# v2_1.net
KiCad netlist of a schematic drawn in Altium Designer
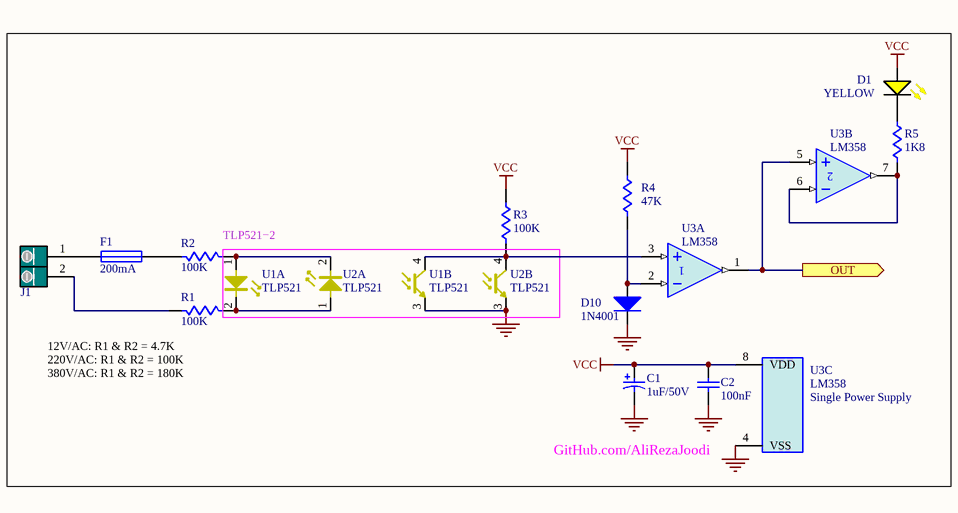
[diagram p0: v2.1.SchDoc]

(export (version "E")
  (design (tool "Eeschema 10.0.6"))
  (components
    (comp (ref "C1")
      (value "1uF/50V")
      (footprint "C_THD_EL_(P2.54-D6-H11)")
      (description "Capacitor, Electrolytic")
      (libsource (lib "Passive") (part "Capacitor_Electrolytic"))
    )
    (comp (ref "C2")
      (value "100nF")
      (footprint "C_THD_CER_(P2.54-D3.5-T1.5)")
      (description "Capacitor, Ceramic Multilayer")
      (libsource (lib "Passive") (part "Capacitor_Ceramic"))
    )
    (comp (ref "D1")
      (value "YELLOW")
      (footprint "LED_THD_5MM_YELLOW")
      (description "LED, Yellow")
      (fields (field (name "MANUFACTURER") "Generic Components") (field (name "PUBLISHER") "Altium Limited"))
      (libsource (lib "Display") (part "LED_YELLOW"))
    )
    (comp (ref "D10")
      (value "1N4001")
      (footprint "DIODE-0.4")
      (description "Default Diode")
      (fields (field (name "MANUFACTURER") "Generic Components") (field (name "PUBLISHER") "Altium Limited"))
      (libsource (lib "Miscellaneous Devices") (part "Diode"))
    )
    (comp (ref "F1")
      (value "200mA")
      (footprint "PIN-W2/E2.8")
      (description "Fuse")
      (fields (field (name "PUBLISHER") "Altium Limited"))
      (libsource (lib "Miscellaneous Devices") (part "Fuse 1"))
    )
    (comp (ref "J1")
      (value "Connector_1x2Pin_Power2")
      (footprint "Phoenix_2PIN_MSTB")
      (description "Connector, Phoenix, 2Pin")
      (libsource (lib "Connector") (part "Connector_1x2Pin_Power2"))
    )
    (comp (ref "R1")
      (value "100K")
      (footprint "AXIAL-0.4")
      (description "Resistor")
      (fields
        (field (name "MANUFACTURER") "Generic Components")
        (field (name "Comment") "Res1")
        (field (name "PUBLISHER") "Altium Limited")
      )
      (libsource (lib "Miscellaneous Devices") (part "Res1"))
    )
    (comp (ref "R2")
      (value "100K")
      (footprint "AXIAL-0.4")
      (description "Resistor")
      (fields
        (field (name "MANUFACTURER") "Generic Components")
        (field (name "Comment") "Res1")
        (field (name "PUBLISHER") "Altium Limited")
      )
      (libsource (lib "Miscellaneous Devices") (part "Res1"))
    )
    (comp (ref "R3")
      (value "100K")
      (footprint "AXIAL-0.4")
      (description "Resistor")
      (fields
        (field (name "MANUFACTURER") "Generic Components")
        (field (name "Comment") "Res1")
        (field (name "PUBLISHER") "Altium Limited")
      )
      (libsource (lib "Miscellaneous Devices") (part "Res1"))
    )
    (comp (ref "R4")
      (value "47K")
      (footprint "AXIAL-0.4")
      (description "Resistor")
      (fields
        (field (name "MANUFACTURER") "Generic Components")
        (field (name "Comment") "Res1")
        (field (name "PUBLISHER") "Altium Limited")
      )
      (libsource (lib "Miscellaneous Devices") (part "Res1"))
    )
    (comp (ref "R5")
      (value "1K8")
      (footprint "AXIAL-0.4")
      (description "Resistor")
      (fields (field (name "MANUFACTURER") "Generic Components") (field (name "PUBLISHER") "Altium Limited"))
      (libsource (lib "Miscellaneous Devices") (part "Res1"))
    )
    (comp (ref "U1")
      (value "TLP521")
      (footprint "DIP_4")
      (description "Phototransistor")
      (fields (field (name "PUBLISHER") "Altium Limited"))
      (libsource (lib "IC") (part "OptoIsolator_Transistor"))
    )
    (comp (ref "U2")
      (value "TLP521")
      (footprint "DIP_4")
      (description "Phototransistor")
      (fields (field (name "PUBLISHER") "Altium Limited"))
      (libsource (lib "IC") (part "OptoIsolator_Transistor"))
    )
    (comp (ref "U3")
      (value "LM358")
      (footprint "DIP_8")
      (description "Dual Low-Power Operational Amplifier")
      (fields (field (name "PUBLISHER") "Altium Limited"))
      (libsource (lib "Op-Amp") (part "LM358"))
    )
  )
  (nets
    (net (code "1") (name "/OUT") (class "Default")
      (node (ref "U3") (pin "1") (pinfunction "OUT_1") (pintype "output"))
      (node (ref "U3") (pin "5") (pinfunction "IN+_5") (pintype "input"))
    )
    (net (code "2") (name "GND") (class "Default")
      (node (ref "C1") (pin "2") (pinfunction "2_2") (pintype "passive"))
      (node (ref "C2") (pin "2") (pinfunction "2_2") (pintype "passive"))
      (node (ref "D10") (pin "2") (pinfunction "K_2") (pintype "passive"))
      (node (ref "U1") (pin "3") (pinfunction "E_3") (pintype "passive"))
      (node (ref "U2") (pin "3") (pinfunction "E_3") (pintype "passive"))
      (node (ref "U3") (pin "4") (pinfunction "VSS_4") (pintype "power_in"))
    )
    (net (code "3") (name "Net-(D1-K)") (class "Default")
      (node (ref "D1") (pin "2") (pinfunction "K_2") (pintype "passive"))
      (node (ref "R5") (pin "2") (pinfunction "2_2") (pintype "passive"))
    )
    (net (code "4") (name "Net-(D10-A)") (class "Default")
      (node (ref "D10") (pin "1") (pinfunction "A_1") (pintype "passive"))
      (node (ref "R4") (pin "2") (pinfunction "2_2") (pintype "passive"))
      (node (ref "U3") (pin "2") (pinfunction "IN-_2") (pintype "input"))
    )
    (net (code "5") (name "Net-(F1-Pad1)") (class "Default")
      (node (ref "F1") (pin "1") (pinfunction "1_1") (pintype "passive"))
      (node (ref "R2") (pin "1") (pinfunction "1_1") (pintype "passive"))
    )
    (net (code "6") (name "Net-(F1-Pad2)") (class "Default")
      (node (ref "F1") (pin "2") (pinfunction "2_2") (pintype "passive"))
      (node (ref "J1") (pin "1") (pinfunction "1_1") (pintype "passive"))
    )
    (net (code "7") (name "Net-(J1-Pad2)") (class "Default")
      (node (ref "J1") (pin "2") (pinfunction "2_2") (pintype "passive"))
      (node (ref "R1") (pin "1") (pinfunction "1_1") (pintype "passive"))
    )
    (net (code "8") (name "Net-(U1A-A)") (class "Default")
      (node (ref "R2") (pin "2") (pinfunction "2_2") (pintype "passive"))
      (node (ref "U1") (pin "1") (pinfunction "A_1") (pintype "power_in"))
      (node (ref "U2") (pin "2") (pinfunction "K_2") (pintype "power_in"))
    )
    (net (code "9") (name "Net-(U1A-K)") (class "Default")
      (node (ref "R1") (pin "2") (pinfunction "2_2") (pintype "passive"))
      (node (ref "U1") (pin "2") (pinfunction "K_2") (pintype "power_in"))
      (node (ref "U2") (pin "1") (pinfunction "A_1") (pintype "power_in"))
    )
    (net (code "10") (name "Net-(U1B-C)") (class "Default")
      (node (ref "R3") (pin "2") (pinfunction "2_2") (pintype "passive"))
      (node (ref "U1") (pin "4") (pinfunction "C_4") (pintype "passive"))
      (node (ref "U2") (pin "4") (pinfunction "C_4") (pintype "passive"))
      (node (ref "U3") (pin "3") (pinfunction "IN+_3") (pintype "input"))
    )
    (net (code "11") (name "Net-(U3B-IN-)") (class "Default")
      (node (ref "R5") (pin "1") (pinfunction "1_1") (pintype "passive"))
      (node (ref "U3") (pin "6") (pinfunction "IN-_6") (pintype "input"))
      (node (ref "U3") (pin "7") (pinfunction "OUT_7") (pintype "output"))
    )
    (net (code "12") (name "VCC") (class "Default")
      (node (ref "C1") (pin "1") (pinfunction "1_1") (pintype "passive"))
      (node (ref "C2") (pin "1") (pinfunction "1_1") (pintype "passive"))
      (node (ref "D1") (pin "1") (pinfunction "A_1") (pintype "passive"))
      (node (ref "R3") (pin "1") (pinfunction "1_1") (pintype "passive"))
      (node (ref "R4") (pin "1") (pinfunction "1_1") (pintype "passive"))
      (node (ref "U3") (pin "8") (pinfunction "VDD_8") (pintype "passive"))
    )
  )
)
